# 4_MCU.net
KiCad netlist of a schematic drawn in Altium Designer
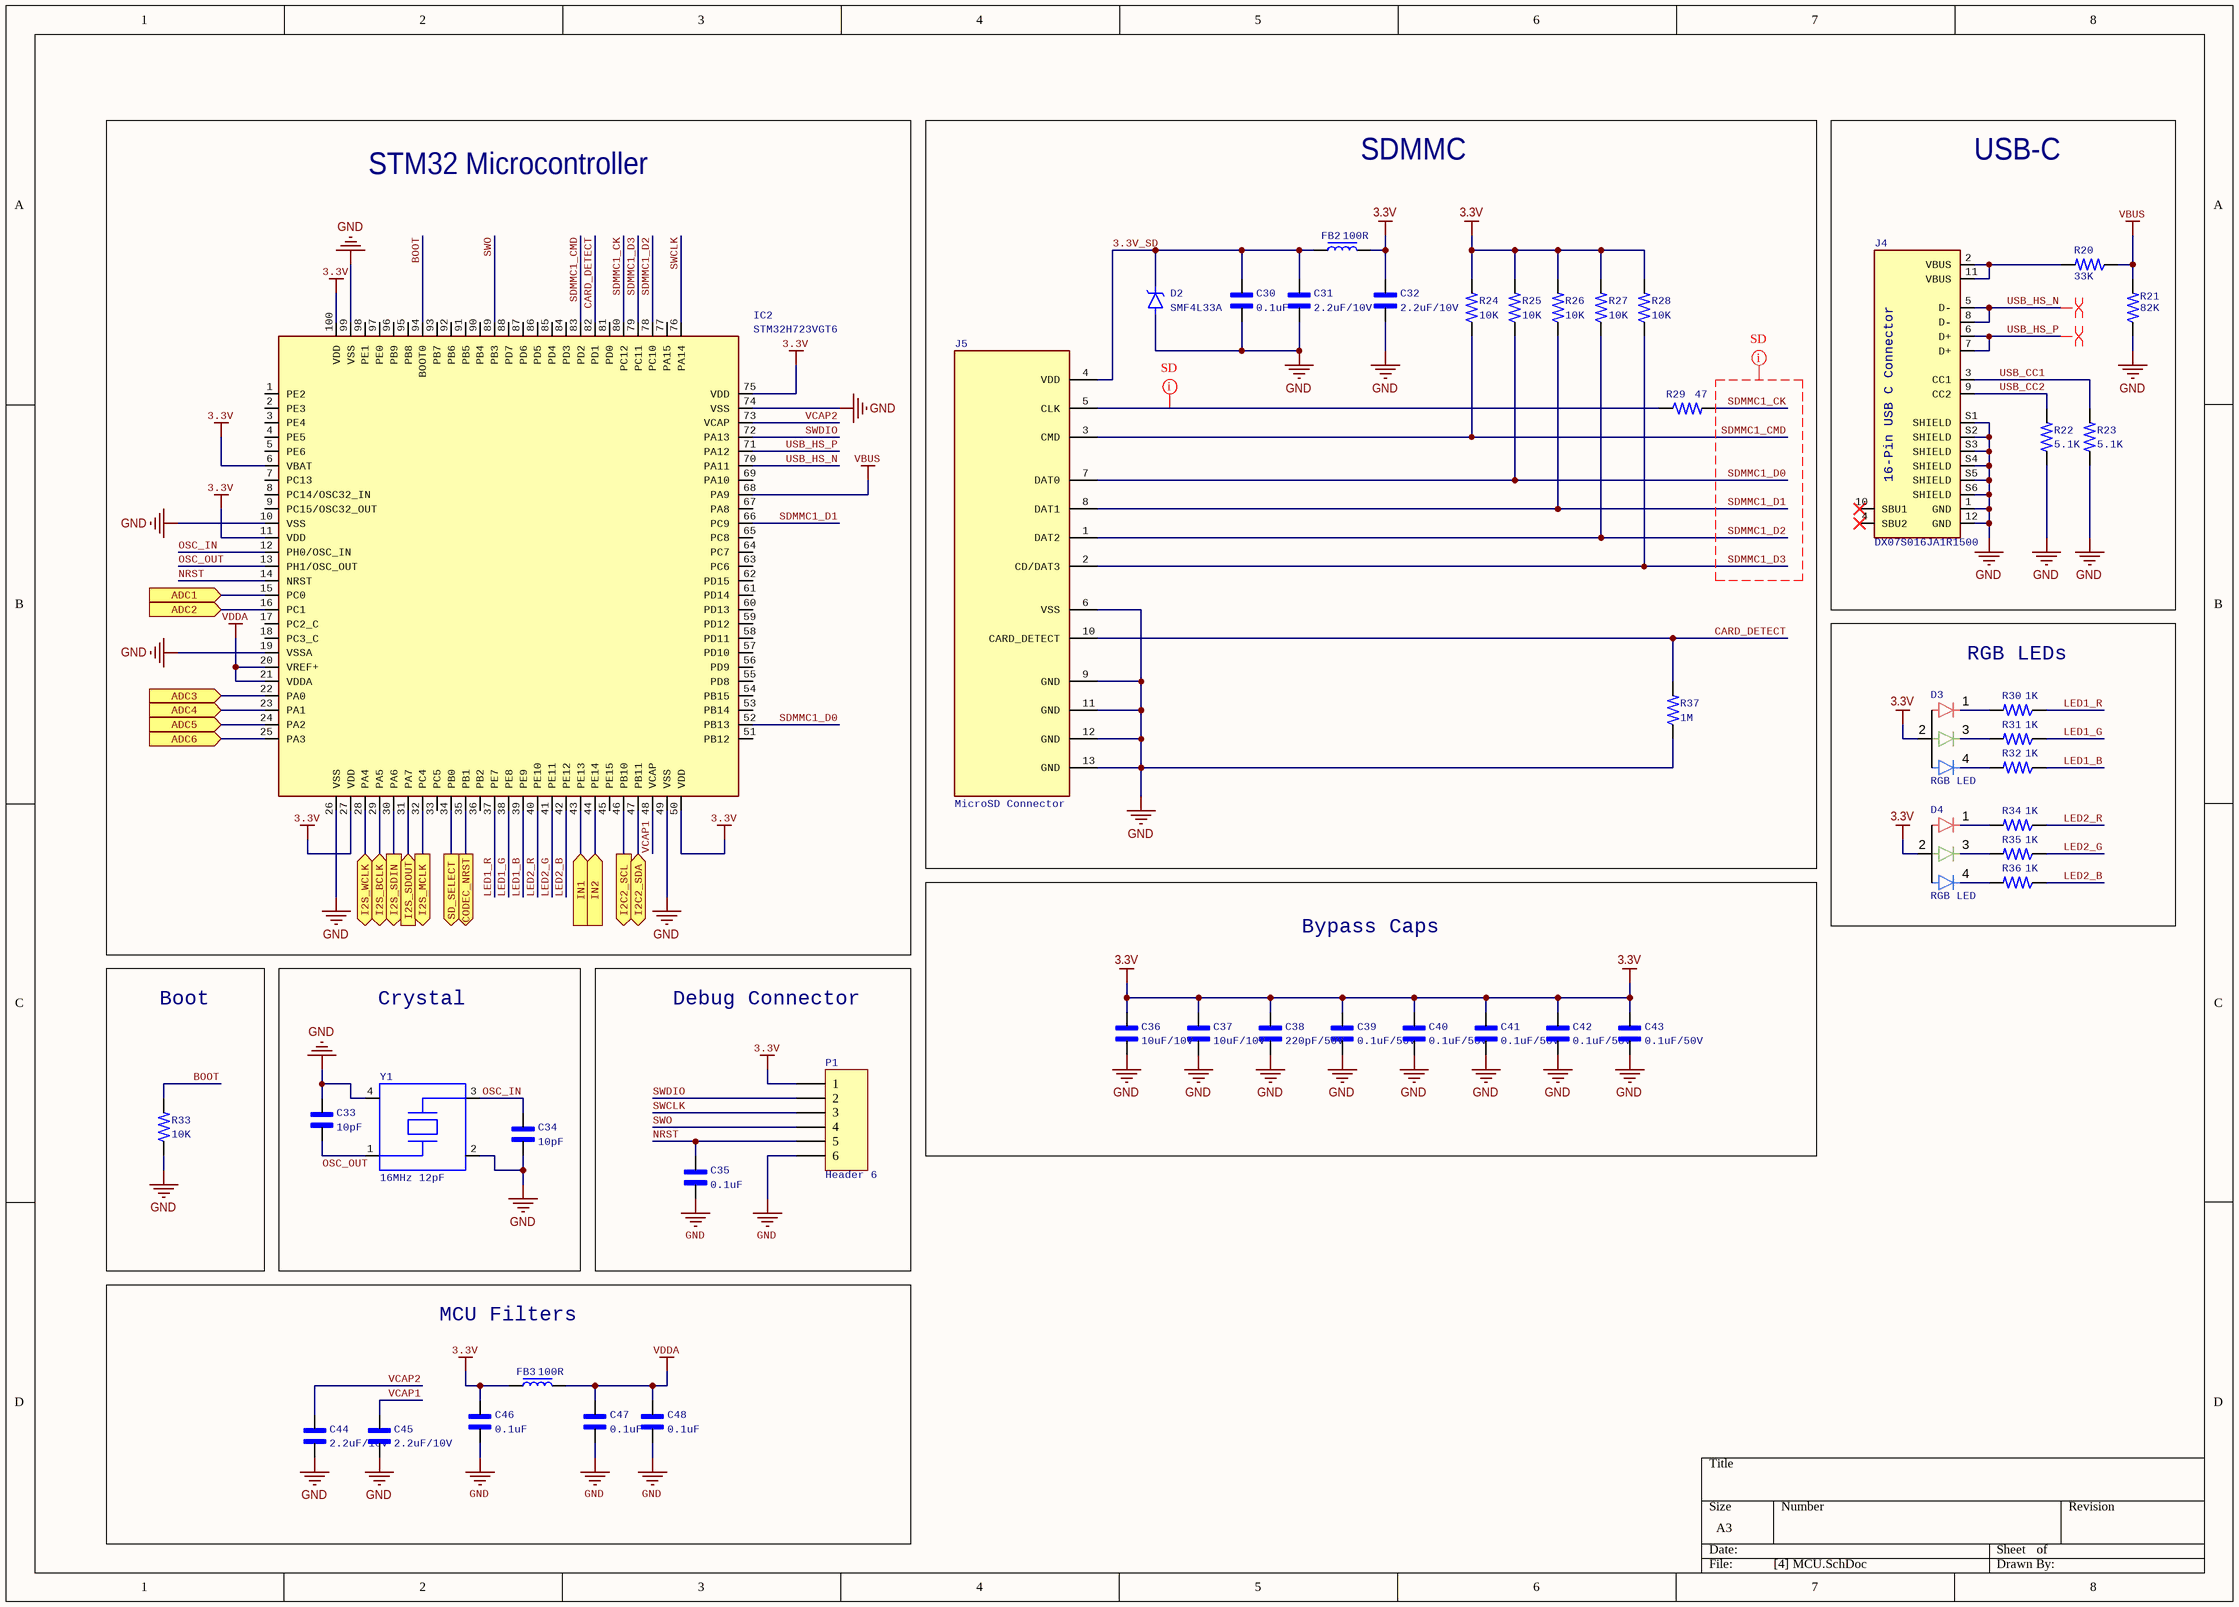
[diagram p0: [4] MCU.SchDoc]

(export (version "E")
  (design (tool "Eeschema 10.0.6"))
  (components
    (comp (ref "C30")
      (value "0.1uF")
      (footprint "C0603")
      (description "MLCC 0.1uF 50V X5R 10% 0603")
      (fields
        (field (name "MANUFACTURER") "TDK")
        (field (name "MANUFACTURER PART NUMBER") "C1608X5R1H104K080AA")
      )
      (libsource (lib "Capacitors") (part "C0603 0.1uF/50V"))
    )
    (comp (ref "C31")
      (value "2.2uF/10V")
      (footprint "C0603")
      (description "MLCC 2.2uF 10V X5R 10% 0603")
      (fields
        (field (name "MANUFACTURER") "Samsung")
        (field (name "MANUFACTURER PART NUMBER") "CL10A225KP8NNNC")
      )
      (libsource (lib "Capacitors") (part "C0603 2.2uF/10V"))
    )
    (comp (ref "C32")
      (value "2.2uF/10V")
      (footprint "C0603")
      (description "MLCC 2.2uF 10V X5R 10% 0603")
      (fields
        (field (name "MANUFACTURER") "Samsung")
        (field (name "MANUFACTURER PART NUMBER") "CL10A225KP8NNNC")
      )
      (libsource (lib "Capacitors") (part "C0603 2.2uF/10V"))
    )
    (comp (ref "C33")
      (value "10pF")
      (footprint "C0603")
      (description "MLCC 10pF 50V X7R 10% 0603")
      (fields
        (field (name "MANUFACTURER") "KEMET")
        (field (name "MANUFACTURER PART NUMBER") "C0603C100K5RACTU")
      )
      (libsource (lib "") (part "C0603 10pF/50V_1"))
    )
    (comp (ref "C34")
      (value "10pF")
      (footprint "C0603")
      (description "MLCC 10pF 50V X7R 10% 0603")
      (fields
        (field (name "MANUFACTURER") "KEMET")
        (field (name "MANUFACTURER PART NUMBER") "C0603C100K5RACTU")
      )
      (libsource (lib "Capacitors") (part "C0603 10pF/50V"))
    )
    (comp (ref "C35")
      (value "0.1uF")
      (footprint "C0603")
      (description "MLCC 0.1uF 50V X5R 10% 0603")
      (fields
        (field (name "MANUFACTURER") "TDK")
        (field (name "MANUFACTURER PART NUMBER") "C1608X5R1H104K080AA")
      )
      (libsource (lib "Capacitors") (part "C0603 0.1uF/50V"))
    )
    (comp (ref "C36")
      (value "10uF/10V")
      (footprint "C0603")
      (description "MLCC 10uF 10V X5R 20% 0603")
      (fields
        (field (name "MANUFACTURER") "KEMET")
        (field (name "MANUFACTURER PART NUMBER") "C0603C106M8PAC7867")
      )
      (libsource (lib "Capacitors") (part "C0603 10uF/10V"))
    )
    (comp (ref "C37")
      (value "10uF/10V")
      (footprint "C0603")
      (description "MLCC 10uF 10V X5R 20% 0603")
      (fields
        (field (name "MANUFACTURER") "KEMET")
        (field (name "MANUFACTURER PART NUMBER") "C0603C106M8PAC7867")
      )
      (libsource (lib "Capacitors") (part "C0603 10uF/10V"))
    )
    (comp (ref "C38")
      (value "220pF/50V")
      (footprint "C0603")
      (description "MLCC 220pF 50V X7R 10% 0603")
      (fields
        (field (name "MANUFACTURER") "KEMET")
        (field (name "MANUFACTURER PART NUMBER") "C0603C221K5RACTU")
      )
      (libsource (lib "Capacitors") (part "C0603 220pF/50V"))
    )
    (comp (ref "C39")
      (value "0.1uF/50V")
      (footprint "C0603")
      (description "MLCC 0.1uF 50V X5R 10% 0603")
      (fields
        (field (name "MANUFACTURER") "TDK")
        (field (name "MANUFACTURER PART NUMBER") "C1608X5R1H104K080AA")
      )
      (libsource (lib "Capacitors") (part "C0603 0.1uF/50V"))
    )
    (comp (ref "C40")
      (value "0.1uF/50V")
      (footprint "C0603")
      (description "MLCC 0.1uF 50V X5R 10% 0603")
      (fields
        (field (name "MANUFACTURER") "TDK")
        (field (name "MANUFACTURER PART NUMBER") "C1608X5R1H104K080AA")
      )
      (libsource (lib "Capacitors") (part "C0603 0.1uF/50V"))
    )
    (comp (ref "C41")
      (value "0.1uF/50V")
      (footprint "C0603")
      (description "MLCC 0.1uF 50V X5R 10% 0603")
      (fields
        (field (name "MANUFACTURER") "TDK")
        (field (name "MANUFACTURER PART NUMBER") "C1608X5R1H104K080AA")
      )
      (libsource (lib "Capacitors") (part "C0603 0.1uF/50V"))
    )
    (comp (ref "C42")
      (value "0.1uF/50V")
      (footprint "C0603")
      (description "MLCC 0.1uF 50V X5R 10% 0603")
      (fields
        (field (name "MANUFACTURER") "TDK")
        (field (name "MANUFACTURER PART NUMBER") "C1608X5R1H104K080AA")
      )
      (libsource (lib "Capacitors") (part "C0603 0.1uF/50V"))
    )
    (comp (ref "C43")
      (value "0.1uF/50V")
      (footprint "C0603")
      (description "MLCC 0.1uF 50V X5R 10% 0603")
      (fields
        (field (name "MANUFACTURER") "TDK")
        (field (name "MANUFACTURER PART NUMBER") "C1608X5R1H104K080AA")
      )
      (libsource (lib "Capacitors") (part "C0603 0.1uF/50V"))
    )
    (comp (ref "C44")
      (value "2.2uF/10V")
      (footprint "C0603")
      (description "MLCC 2.2uF 10V X5R 10% 0603")
      (fields
        (field (name "MANUFACTURER") "Samsung")
        (field (name "MANUFACTURER PART NUMBER") "CL10A225KP8NNNC")
      )
      (libsource (lib "Capacitors") (part "C0603 2.2uF/10V"))
    )
    (comp (ref "C45")
      (value "2.2uF/10V")
      (footprint "C0603")
      (description "MLCC 2.2uF 10V X5R 10% 0603")
      (fields
        (field (name "MANUFACTURER") "Samsung")
        (field (name "MANUFACTURER PART NUMBER") "CL10A225KP8NNNC")
      )
      (libsource (lib "Capacitors") (part "C0603 2.2uF/10V"))
    )
    (comp (ref "C46")
      (value "0.1uF")
      (footprint "C0603")
      (description "MLCC 0.1uF 50V X5R 10% 0603")
      (fields
        (field (name "MANUFACTURER") "TDK")
        (field (name "MANUFACTURER PART NUMBER") "C1608X5R1H104K080AA")
      )
      (libsource (lib "Capacitors") (part "C0603 0.1uF/50V"))
    )
    (comp (ref "C47")
      (value "0.1uF")
      (footprint "C0603")
      (description "MLCC 0.1uF 50V X5R 10% 0603")
      (fields
        (field (name "MANUFACTURER") "TDK")
        (field (name "MANUFACTURER PART NUMBER") "C1608X5R1H104K080AA")
      )
      (libsource (lib "Capacitors") (part "C0603 0.1uF/50V"))
    )
    (comp (ref "C48")
      (value "0.1uF")
      (footprint "C0603")
      (description "MLCC 0.1uF 50V X5R 10% 0603")
      (fields
        (field (name "MANUFACTURER") "TDK")
        (field (name "MANUFACTURER PART NUMBER") "C1608X5R1H104K080AA")
      )
      (libsource (lib "Capacitors") (part "C0603 0.1uF/50V"))
    )
    (comp (ref "D2")
      (value "SMF4L33A")
      (footprint "SOD-123FL")
      (description "TVS DIODE, 2KW, 33V, UNIDIR, SOD-123FL")
      (fields (field (name "MANUFACTURER") "Littelfuse"))
      (libsource (lib "DiscreteSemi") (part "ESD Diode SMF4L33A"))
    )
    (comp (ref "D3")
      (value "RGB LED")
      (footprint "RGB LED CA")
      (description "LED RGB CLEAR T-1 3/4 T/H CA")
      (fields
        (field (name "MANUFACTURER") "Kingbright")
        (field (name "MANUFACTURER PART NUMBER") "WP154A4SEJ3VBDZGC/CA")
      )
      (libsource (lib "LED") (part "RGB LED CA PTH"))
    )
    (comp (ref "D4")
      (value "RGB LED")
      (footprint "RGB LED CA")
      (description "LED RGB CLEAR T-1 3/4 T/H CA")
      (fields
        (field (name "MANUFACTURER") "Kingbright")
        (field (name "MANUFACTURER PART NUMBER") "WP154A4SEJ3VBDZGC/CA")
      )
      (libsource (lib "LED") (part "RGB LED CA PTH"))
    )
    (comp (ref "FB2")
      (value "100R")
      (footprint "FB_0603")
      (description "Ferrite Bead SMD 0603")
      (libsource (lib "Schematic-Lib-PhilsLab") (part "FB_0603"))
    )
    (comp (ref "FB3")
      (value "100R")
      (footprint "FB_0603")
      (description "Ferrite Bead SMD 0603")
      (libsource (lib "Schematic-Lib-PhilsLab") (part "FB_0603"))
    )
    (comp (ref "IC2")
      (value "STM32H723VGT6")
      (footprint "QFP-100")
      (description "MCU 32-bit ARM Cortex M7 RISC 1MB Flash 1.8V/2.5V/3.3V 100-Pin LQFP Tray")
      (fields (field (name "MANUFACTURER") "STMicroelectronics"))
      (libsource (lib "MCUs") (part "STM32H723VGT6"))
    )
    (comp (ref "J4")
      (value "DX07S016JA1R1500")
      (footprint "USB-C_JAE_DX07S016JA1R1500")
      (description "USB-C (USB TYPE-C) USB 2.0 Receptacle Connector 24 (16+8 Dummy) SMT, Right Angle; Through Hole")
      (fields (field (name "MANUFACTURER") "JAE Electronics"))
      (libsource (lib "Connectors") (part "USB C 16-Pin"))
    )
    (comp (ref "J5")
      (value "MicroSD Connector")
      (footprint "DM3CSSF")
      (description "Connector, Memory, Micro Sd, DM3CS-SF")
      (fields (field (name "MANUFACTURER") "Hirose") (field (name "MANUFACTURER PART NUMBER") "DM3CS-SF"))
      (libsource (lib "Connectors") (part "DM3CS-SF"))
    )
    (comp (ref "P1")
      (value "Header 6")
      (footprint "HDR1X6")
      (description "Header, 6-Pin")
      (fields (field (name "PUBLISHER") "Altium Limited"))
      (libsource (lib "Miscellaneous Connectors") (part "Header 6"))
    )
    (comp (ref "R20")
      (value "33K")
      (footprint "R0603")
      (description "RES 0603 33K 1% 1/10W")
      (fields
        (field (name "MANUFACTURER") "Yageo")
        (field (name "MANUFACTURER PART NUMBER") "AC0603FR-1333KL")
      )
      (libsource (lib "Resistors") (part "R0603 33K"))
    )
    (comp (ref "R21")
      (value "82K")
      (footprint "R0603")
      (description "RES 0603 82K OHM 0.5% 1/10W")
      (fields
        (field (name "MANUFACTURER") "Yageo")
        (field (name "MANUFACTURER PART NUMBER") "RC0603FR-0782KL")
      )
      (libsource (lib "Resistors") (part "R0603 82K"))
    )
    (comp (ref "R22")
      (value "5.1K")
      (footprint "R0603")
      (description "RES 0603 5.1K OHM 1% 1/10W")
      (fields
        (field (name "MANUFACTURER") "Yageo")
        (field (name "MANUFACTURER PART NUMBER") "RC0603FR-075K1L")
      )
      (libsource (lib "Resistors") (part "R0603 5.1K"))
    )
    (comp (ref "R23")
      (value "5.1K")
      (footprint "R0603")
      (description "RES 0603 5.1K OHM 1% 1/10W")
      (fields
        (field (name "MANUFACTURER") "Yageo")
        (field (name "MANUFACTURER PART NUMBER") "RC0603FR-075K1L")
      )
      (libsource (lib "Resistors") (part "R0603 5.1K"))
    )
    (comp (ref "R24")
      (value "10K")
      (footprint "R0603")
      (description "RES 0603 10K OHM 1% 1/10W")
      (fields
        (field (name "MANUFACTURER") "Yageo")
        (field (name "MANUFACTURER PART NUMBER") "RC0603FR-1310KL")
      )
      (libsource (lib "Resistors") (part "R0603 10K"))
    )
    (comp (ref "R25")
      (value "10K")
      (footprint "R0603")
      (description "RES 0603 10K OHM 1% 1/10W")
      (fields
        (field (name "MANUFACTURER") "Yageo")
        (field (name "MANUFACTURER PART NUMBER") "RC0603FR-1310KL")
      )
      (libsource (lib "Resistors") (part "R0603 10K"))
    )
    (comp (ref "R26")
      (value "10K")
      (footprint "R0603")
      (description "RES 0603 10K OHM 1% 1/10W")
      (fields
        (field (name "MANUFACTURER") "Yageo")
        (field (name "MANUFACTURER PART NUMBER") "RC0603FR-1310KL")
      )
      (libsource (lib "Resistors") (part "R0603 10K"))
    )
    (comp (ref "R27")
      (value "10K")
      (footprint "R0603")
      (description "RES 0603 10K OHM 1% 1/10W")
      (fields
        (field (name "MANUFACTURER") "Yageo")
        (field (name "MANUFACTURER PART NUMBER") "RC0603FR-1310KL")
      )
      (libsource (lib "Resistors") (part "R0603 10K"))
    )
    (comp (ref "R28")
      (value "10K")
      (footprint "R0603")
      (description "RES 0603 10K OHM 1% 1/10W")
      (fields
        (field (name "MANUFACTURER") "Yageo")
        (field (name "MANUFACTURER PART NUMBER") "RC0603FR-1310KL")
      )
      (libsource (lib "Resistors") (part "R0603 10K"))
    )
    (comp (ref "R29")
      (value "47")
      (footprint "R0603")
      (description "RES 0603 47 1% 1/10W")
      (fields
        (field (name "MANUFACTURER") "Yageo")
        (field (name "MANUFACTURER PART NUMBER") "RC0603FR-0747RL")
      )
      (libsource (lib "Resistors") (part "R0603 47"))
    )
    (comp (ref "R30")
      (value "1K")
      (footprint "R0603")
      (description "RES 0603 1K OHM 1% 1/10W")
      (fields
        (field (name "MANUFACTURER") "Yageo")
        (field (name "MANUFACTURER PART NUMBER") "RC0603FR-071KL")
      )
      (libsource (lib "Resistors") (part "R0603 1K"))
    )
    (comp (ref "R31")
      (value "1K")
      (footprint "R0603")
      (description "RES 0603 1K OHM 1% 1/10W")
      (fields
        (field (name "MANUFACTURER") "Yageo")
        (field (name "MANUFACTURER PART NUMBER") "RC0603FR-071KL")
      )
      (libsource (lib "Resistors") (part "R0603 1K"))
    )
    (comp (ref "R32")
      (value "1K")
      (footprint "R0603")
      (description "RES 0603 1K OHM 1% 1/10W")
      (fields
        (field (name "MANUFACTURER") "Yageo")
        (field (name "MANUFACTURER PART NUMBER") "RC0603FR-071KL")
      )
      (libsource (lib "Resistors") (part "R0603 1K"))
    )
    (comp (ref "R33")
      (value "10K")
      (footprint "R0603")
      (description "RES 0603 10K OHM 1% 1/10W")
      (fields
        (field (name "MANUFACTURER") "Yageo")
        (field (name "MANUFACTURER PART NUMBER") "RC0603FR-1310KL")
      )
      (libsource (lib "Resistors") (part "R0603 10K"))
    )
    (comp (ref "R34")
      (value "1K")
      (footprint "R0603")
      (description "RES 0603 1K OHM 1% 1/10W")
      (fields
        (field (name "MANUFACTURER") "Yageo")
        (field (name "MANUFACTURER PART NUMBER") "RC0603FR-071KL")
      )
      (libsource (lib "Resistors") (part "R0603 1K"))
    )
    (comp (ref "R35")
      (value "1K")
      (footprint "R0603")
      (description "RES 0603 1K OHM 1% 1/10W")
      (fields
        (field (name "MANUFACTURER") "Yageo")
        (field (name "MANUFACTURER PART NUMBER") "RC0603FR-071KL")
      )
      (libsource (lib "Resistors") (part "R0603 1K"))
    )
    (comp (ref "R36")
      (value "1K")
      (footprint "R0603")
      (description "RES 0603 1K OHM 1% 1/10W")
      (fields
        (field (name "MANUFACTURER") "Yageo")
        (field (name "MANUFACTURER PART NUMBER") "RC0603FR-071KL")
      )
      (libsource (lib "Resistors") (part "R0603 1K"))
    )
    (comp (ref "R37")
      (value "1M")
      (footprint "R0603")
      (description "RES SMD 1M OHM 1% 1/10W 0603")
      (fields
        (field (name "MANUFACTURER") "Yageo")
        (field (name "MANUFACTURER PART NUMBER") "RC0603FR-071ML")
      )
      (libsource (lib "Resistors") (part "R0603 1M"))
    )
    (comp (ref "Y1")
      (value "16MHz 12pF")
      (footprint "XTAL 3.2 x 2.5 mm")
      (description "Crystal 16MHz ±50ppm (Tol) ±100ppm (Stability) 12pF FUND 80Ohm 4-Pin SMD T/R")
      (fields
        (field (name "MANUFACTURER") "Kyocera AVX")
        (field (name "MANUFACTURER PART NUMBER") "CX3225SB16000H0PSTC1")
      )
      (libsource (lib "Clocks") (part "XTAL 16MHz 12pF"))
    )
  )
  (nets
    (net (code "1") (name "/3.3V_SD") (class "Default")
      (node (ref "C30") (pin "1") (pinfunction "1_1") (pintype "passive"))
      (node (ref "C31") (pin "1") (pinfunction "1_1") (pintype "passive"))
      (node (ref "D2") (pin "C") (pinfunction "C_C") (pintype "passive"))
      (node (ref "FB2") (pin "1") (pinfunction "1_1") (pintype "passive"))
      (node (ref "J5") (pin "4") (pinfunction "VDD_4") (pintype "passive"))
    )
    (net (code "2") (name "/ADC1") (class "Default")
      (node (ref "IC2") (pin "15") (pinfunction "PC0_15") (pintype "passive"))
    )
    (net (code "3") (name "/ADC2") (class "Default")
      (node (ref "IC2") (pin "16") (pinfunction "PC1_16") (pintype "passive"))
    )
    (net (code "4") (name "/ADC3") (class "Default")
      (node (ref "IC2") (pin "22") (pinfunction "PA0_22") (pintype "passive"))
    )
    (net (code "5") (name "/ADC4") (class "Default")
      (node (ref "IC2") (pin "23") (pinfunction "PA1_23") (pintype "passive"))
    )
    (net (code "6") (name "/ADC5") (class "Default")
      (node (ref "IC2") (pin "24") (pinfunction "PA2_24") (pintype "passive"))
    )
    (net (code "7") (name "/ADC6") (class "Default")
      (node (ref "IC2") (pin "25") (pinfunction "PA3_25") (pintype "passive"))
    )
    (net (code "8") (name "/BOOT") (class "Default")
      (node (ref "IC2") (pin "94") (pinfunction "BOOT0_94") (pintype "passive"))
      (node (ref "R33") (pin "2") (pinfunction "2_2") (pintype "passive"))
    )
    (net (code "9") (name "/CARD_DETECT") (class "Default")
      (node (ref "IC2") (pin "82") (pinfunction "PD1_82") (pintype "passive"))
      (node (ref "J5") (pin "10") (pinfunction "CARD_DETECT_10") (pintype "passive"))
      (node (ref "R37") (pin "2") (pinfunction "2_2") (pintype "passive"))
    )
    (net (code "10") (name "/CODEC_NRST") (class "Default")
      (node (ref "IC2") (pin "35") (pinfunction "PB1_35") (pintype "passive"))
    )
    (net (code "11") (name "/I2C2_SCL") (class "Default")
      (node (ref "IC2") (pin "46") (pinfunction "PB10_46") (pintype "passive"))
    )
    (net (code "12") (name "/I2C2_SDA") (class "Default")
      (node (ref "IC2") (pin "47") (pinfunction "PB11_47") (pintype "passive"))
    )
    (net (code "13") (name "/I2S_BCLK") (class "Default")
      (node (ref "IC2") (pin "29") (pinfunction "PA5_29") (pintype "passive"))
    )
    (net (code "14") (name "/I2S_MCLK") (class "Default")
      (node (ref "IC2") (pin "32") (pinfunction "PC4_32") (pintype "passive"))
    )
    (net (code "15") (name "/I2S_SDIN") (class "Default")
      (node (ref "IC2") (pin "30") (pinfunction "PA6_30") (pintype "passive"))
    )
    (net (code "16") (name "/I2S_SDOUT") (class "Default")
      (node (ref "IC2") (pin "31") (pinfunction "PA7_31") (pintype "passive"))
    )
    (net (code "17") (name "/I2S_WCLK") (class "Default")
      (node (ref "IC2") (pin "28") (pinfunction "PA4_28") (pintype "passive"))
    )
    (net (code "18") (name "/IN1") (class "Default")
      (node (ref "IC2") (pin "43") (pinfunction "PE13_43") (pintype "passive"))
    )
    (net (code "19") (name "/IN2") (class "Default")
      (node (ref "IC2") (pin "44") (pinfunction "PE14_44") (pintype "passive"))
    )
    (net (code "20") (name "/LED1_B") (class "Default")
      (node (ref "IC2") (pin "39") (pinfunction "PE9_39") (pintype "passive"))
      (node (ref "R32") (pin "1") (pinfunction "1_1") (pintype "passive"))
    )
    (net (code "21") (name "/LED1_G") (class "Default")
      (node (ref "IC2") (pin "38") (pinfunction "PE8_38") (pintype "passive"))
      (node (ref "R31") (pin "1") (pinfunction "1_1") (pintype "passive"))
    )
    (net (code "22") (name "/LED1_R") (class "Default")
      (node (ref "IC2") (pin "37") (pinfunction "PE7_37") (pintype "passive"))
      (node (ref "R30") (pin "1") (pinfunction "1_1") (pintype "passive"))
    )
    (net (code "23") (name "/LED2_B") (class "Default")
      (node (ref "IC2") (pin "42") (pinfunction "PE12_42") (pintype "passive"))
      (node (ref "R36") (pin "1") (pinfunction "1_1") (pintype "passive"))
    )
    (net (code "24") (name "/LED2_G") (class "Default")
      (node (ref "IC2") (pin "41") (pinfunction "PE11_41") (pintype "passive"))
      (node (ref "R35") (pin "1") (pinfunction "1_1") (pintype "passive"))
    )
    (net (code "25") (name "/LED2_R") (class "Default")
      (node (ref "IC2") (pin "40") (pinfunction "PE10_40") (pintype "passive"))
      (node (ref "R34") (pin "1") (pinfunction "1_1") (pintype "passive"))
    )
    (net (code "26") (name "/NRST") (class "Default")
      (node (ref "C35") (pin "1") (pinfunction "1_1") (pintype "passive"))
      (node (ref "IC2") (pin "14") (pinfunction "NRST_14") (pintype "passive"))
      (node (ref "P1") (pin "5") (pinfunction "5_5") (pintype "passive"))
    )
    (net (code "27") (name "/OSC_IN") (class "Default")
      (node (ref "C34") (pin "2") (pinfunction "2_2") (pintype "passive"))
      (node (ref "IC2") (pin "12") (pinfunction "PH0/OSC_IN_12") (pintype "passive"))
      (node (ref "Y1") (pin "3") (pinfunction "3_3") (pintype "passive"))
    )
    (net (code "28") (name "/OSC_OUT") (class "Default")
      (node (ref "C33") (pin "2") (pinfunction "2_2") (pintype "passive"))
      (node (ref "IC2") (pin "13") (pinfunction "PH1/OSC_OUT_13") (pintype "passive"))
      (node (ref "Y1") (pin "1") (pinfunction "1_1") (pintype "passive"))
    )
    (net (code "29") (name "/SDMMC1_CK") (class "Default")
      (node (ref "IC2") (pin "80") (pinfunction "PC12_80") (pintype "passive"))
      (node (ref "R29") (pin "2") (pinfunction "2_2") (pintype "passive"))
    )
    (net (code "30") (name "/SDMMC1_CMD") (class "Default")
      (node (ref "IC2") (pin "83") (pinfunction "PD2_83") (pintype "passive"))
      (node (ref "J5") (pin "3") (pinfunction "CMD_3") (pintype "passive"))
      (node (ref "R24") (pin "1") (pinfunction "1_1") (pintype "passive"))
    )
    (net (code "31") (name "/SDMMC1_D0") (class "Default")
      (node (ref "IC2") (pin "52") (pinfunction "PB13_52") (pintype "passive"))
      (node (ref "J5") (pin "7") (pinfunction "DAT0_7") (pintype "passive"))
      (node (ref "R25") (pin "1") (pinfunction "1_1") (pintype "passive"))
    )
    (net (code "32") (name "/SDMMC1_D1") (class "Default")
      (node (ref "IC2") (pin "66") (pinfunction "PC9_66") (pintype "passive"))
      (node (ref "J5") (pin "8") (pinfunction "DAT1_8") (pintype "passive"))
      (node (ref "R26") (pin "1") (pinfunction "1_1") (pintype "passive"))
    )
    (net (code "33") (name "/SDMMC1_D2") (class "Default")
      (node (ref "IC2") (pin "78") (pinfunction "PC10_78") (pintype "passive"))
      (node (ref "J5") (pin "1") (pinfunction "DAT2_1") (pintype "passive"))
      (node (ref "R27") (pin "1") (pinfunction "1_1") (pintype "passive"))
    )
    (net (code "34") (name "/SDMMC1_D3") (class "Default")
      (node (ref "IC2") (pin "79") (pinfunction "PC11_79") (pintype "passive"))
      (node (ref "J5") (pin "2") (pinfunction "CD/DAT3_2") (pintype "passive"))
      (node (ref "R28") (pin "1") (pinfunction "1_1") (pintype "passive"))
    )
    (net (code "35") (name "/SD_SELECT") (class "Default")
      (node (ref "IC2") (pin "34") (pinfunction "PB0_34") (pintype "passive"))
    )
    (net (code "36") (name "/SWCLK") (class "Default")
      (node (ref "IC2") (pin "76") (pinfunction "PA14_76") (pintype "passive"))
      (node (ref "P1") (pin "3") (pinfunction "3_3") (pintype "passive"))
    )
    (net (code "37") (name "/SWDIO") (class "Default")
      (node (ref "IC2") (pin "72") (pinfunction "PA13_72") (pintype "passive"))
      (node (ref "P1") (pin "2") (pinfunction "2_2") (pintype "passive"))
    )
    (net (code "38") (name "/SWO") (class "Default")
      (node (ref "IC2") (pin "89") (pinfunction "PB3_89") (pintype "passive"))
      (node (ref "P1") (pin "4") (pinfunction "4_4") (pintype "passive"))
    )
    (net (code "39") (name "/USB_CC1") (class "Default")
      (node (ref "J4") (pin "3") (pinfunction "CC1_3") (pintype "passive"))
      (node (ref "R23") (pin "2") (pinfunction "2_2") (pintype "passive"))
    )
    (net (code "40") (name "/USB_CC2") (class "Default")
      (node (ref "J4") (pin "9") (pinfunction "CC2_9") (pintype "passive"))
      (node (ref "R22") (pin "2") (pinfunction "2_2") (pintype "passive"))
    )
    (net (code "41") (name "/USB_HS_N") (class "Default")
      (node (ref "IC2") (pin "70") (pinfunction "PA11_70") (pintype "passive"))
      (node (ref "J4") (pin "5") (pinfunction "D-_5") (pintype "passive"))
      (node (ref "J4") (pin "8") (pinfunction "D-_8") (pintype "passive"))
    )
    (net (code "42") (name "/USB_HS_P") (class "Default")
      (node (ref "IC2") (pin "71") (pinfunction "PA12_71") (pintype "passive"))
      (node (ref "J4") (pin "6") (pinfunction "D+_6") (pintype "passive"))
      (node (ref "J4") (pin "7") (pinfunction "D+_7") (pintype "passive"))
    )
    (net (code "43") (name "/VCAP1") (class "Default")
      (node (ref "C45") (pin "1") (pinfunction "1_1") (pintype "passive"))
      (node (ref "IC2") (pin "48") (pinfunction "VCAP_48") (pintype "passive"))
    )
    (net (code "44") (name "/VCAP2") (class "Default")
      (node (ref "C44") (pin "1") (pinfunction "1_1") (pintype "passive"))
      (node (ref "IC2") (pin "73") (pinfunction "VCAP_73") (pintype "passive"))
    )
    (net (code "45") (name "3.3V") (class "Default")
      (node (ref "C32") (pin "1") (pinfunction "1_1") (pintype "passive"))
      (node (ref "C36") (pin "1") (pinfunction "1_1") (pintype "passive"))
      (node (ref "C37") (pin "1") (pinfunction "1_1") (pintype "passive"))
      (node (ref "C38") (pin "1") (pinfunction "1_1") (pintype "passive"))
      (node (ref "C39") (pin "1") (pinfunction "1_1") (pintype "passive"))
      (node (ref "C40") (pin "1") (pinfunction "1_1") (pintype "passive"))
      (node (ref "C41") (pin "1") (pinfunction "1_1") (pintype "passive"))
      (node (ref "C42") (pin "1") (pinfunction "1_1") (pintype "passive"))
      (node (ref "C43") (pin "1") (pinfunction "1_1") (pintype "passive"))
      (node (ref "C46") (pin "1") (pinfunction "1_1") (pintype "passive"))
      (node (ref "D3") (pin "2") (pinfunction "2_2") (pintype "passive"))
      (node (ref "D4") (pin "2") (pinfunction "2_2") (pintype "passive"))
      (node (ref "FB2") (pin "2") (pinfunction "2_2") (pintype "passive"))
      (node (ref "FB3") (pin "1") (pinfunction "1_1") (pintype "passive"))
      (node (ref "IC2") (pin "100") (pinfunction "VDD_100") (pintype "passive"))
      (node (ref "IC2") (pin "11") (pinfunction "VDD_11") (pintype "passive"))
      (node (ref "IC2") (pin "27") (pinfunction "VDD_27") (pintype "passive"))
      (node (ref "IC2") (pin "50") (pinfunction "VDD_50") (pintype "passive"))
      (node (ref "IC2") (pin "6") (pinfunction "VBAT_6") (pintype "passive"))
      (node (ref "IC2") (pin "75") (pinfunction "VDD_75") (pintype "passive"))
      (node (ref "P1") (pin "1") (pinfunction "1_1") (pintype "passive"))
      (node (ref "R24") (pin "2") (pinfunction "2_2") (pintype "passive"))
      (node (ref "R25") (pin "2") (pinfunction "2_2") (pintype "passive"))
      (node (ref "R26") (pin "2") (pinfunction "2_2") (pintype "passive"))
      (node (ref "R27") (pin "2") (pinfunction "2_2") (pintype "passive"))
      (node (ref "R28") (pin "2") (pinfunction "2_2") (pintype "passive"))
    )
    (net (code "46") (name "GND") (class "Default")
      (node (ref "C30") (pin "2") (pinfunction "2_2") (pintype "passive"))
      (node (ref "C31") (pin "2") (pinfunction "2_2") (pintype "passive"))
      (node (ref "C32") (pin "2") (pinfunction "2_2") (pintype "passive"))
      (node (ref "C33") (pin "1") (pinfunction "1_1") (pintype "passive"))
      (node (ref "C34") (pin "1") (pinfunction "1_1") (pintype "passive"))
      (node (ref "C35") (pin "2") (pinfunction "2_2") (pintype "passive"))
      (node (ref "C36") (pin "2") (pinfunction "2_2") (pintype "passive"))
      (node (ref "C37") (pin "2") (pinfunction "2_2") (pintype "passive"))
      (node (ref "C38") (pin "2") (pinfunction "2_2") (pintype "passive"))
      (node (ref "C39") (pin "2") (pinfunction "2_2") (pintype "passive"))
      (node (ref "C40") (pin "2") (pinfunction "2_2") (pintype "passive"))
      (node (ref "C41") (pin "2") (pinfunction "2_2") (pintype "passive"))
      (node (ref "C42") (pin "2") (pinfunction "2_2") (pintype "passive"))
      (node (ref "C43") (pin "2") (pinfunction "2_2") (pintype "passive"))
      (node (ref "C44") (pin "2") (pinfunction "2_2") (pintype "passive"))
      (node (ref "C45") (pin "2") (pinfunction "2_2") (pintype "passive"))
      (node (ref "C46") (pin "2") (pinfunction "2_2") (pintype "passive"))
      (node (ref "C47") (pin "2") (pinfunction "2_2") (pintype "passive"))
      (node (ref "C48") (pin "2") (pinfunction "2_2") (pintype "passive"))
      (node (ref "D2") (pin "A") (pinfunction "A_A") (pintype "passive"))
      (node (ref "IC2") (pin "10") (pinfunction "VSS_10") (pintype "passive"))
      (node (ref "IC2") (pin "19") (pinfunction "VSSA_19") (pintype "passive"))
      (node (ref "IC2") (pin "26") (pinfunction "VSS_26") (pintype "passive"))
      (node (ref "IC2") (pin "49") (pinfunction "VSS_49") (pintype "passive"))
      (node (ref "IC2") (pin "74") (pinfunction "VSS_74") (pintype "passive"))
      (node (ref "IC2") (pin "99") (pinfunction "VSS_99") (pintype "passive"))
      (node (ref "J4") (pin "1") (pinfunction "GND_1") (pintype "power_in"))
      (node (ref "J4") (pin "12") (pinfunction "GND_12") (pintype "power_in"))
      (node (ref "J4") (pin "S1") (pinfunction "SHIELD_S1") (pintype "passive"))
      (node (ref "J4") (pin "S2") (pinfunction "SHIELD_S2") (pintype "passive"))
      (node (ref "J4") (pin "S3") (pinfunction "SHIELD_S3") (pintype "passive"))
      (node (ref "J4") (pin "S4") (pinfunction "SHIELD_S4") (pintype "passive"))
      (node (ref "J4") (pin "S5") (pinfunction "SHIELD_S5") (pintype "passive"))
      (node (ref "J4") (pin "S6") (pinfunction "SHIELD_S6") (pintype "passive"))
      (node (ref "J5") (pin "11") (pinfunction "GND_11") (pintype "passive"))
      (node (ref "J5") (pin "12") (pinfunction "GND_12") (pintype "passive"))
      (node (ref "J5") (pin "13") (pinfunction "GND_13") (pintype "passive"))
      (node (ref "J5") (pin "6") (pinfunction "VSS_6") (pintype "passive"))
      (node (ref "J5") (pin "9") (pinfunction "GND_9") (pintype "passive"))
      (node (ref "P1") (pin "6") (pinfunction "6_6") (pintype "passive"))
      (node (ref "R21") (pin "1") (pinfunction "1_1") (pintype "passive"))
      (node (ref "R22") (pin "1") (pinfunction "1_1") (pintype "passive"))
      (node (ref "R23") (pin "1") (pinfunction "1_1") (pintype "passive"))
      (node (ref "R33") (pin "1") (pinfunction "1_1") (pintype "passive"))
      (node (ref "R37") (pin "1") (pinfunction "1_1") (pintype "passive"))
      (node (ref "Y1") (pin "2") (pinfunction "2_2") (pintype "passive"))
      (node (ref "Y1") (pin "4") (pinfunction "4_4") (pintype "passive"))
    )
    (net (code "47") (name "Net-(D3-Pad3)") (class "Default")
      (node (ref "D3") (pin "3") (pinfunction "3_3") (pintype "passive"))
      (node (ref "R31") (pin "2") (pinfunction "2_2") (pintype "passive"))
    )
    (net (code "48") (name "Net-(D3-Pad4)") (class "Default")
      (node (ref "D3") (pin "4") (pinfunction "4_4") (pintype "passive"))
      (node (ref "R32") (pin "2") (pinfunction "2_2") (pintype "passive"))
    )
    (net (code "49") (name "Net-(D3-R)") (class "Default")
      (node (ref "D3") (pin "1") (pinfunction "R_1") (pintype "passive"))
      (node (ref "R30") (pin "2") (pinfunction "2_2") (pintype "passive"))
    )
    (net (code "50") (name "Net-(D4-Pad3)") (class "Default")
      (node (ref "D4") (pin "3") (pinfunction "3_3") (pintype "passive"))
      (node (ref "R35") (pin "2") (pinfunction "2_2") (pintype "passive"))
    )
    (net (code "51") (name "Net-(D4-Pad4)") (class "Default")
      (node (ref "D4") (pin "4") (pinfunction "4_4") (pintype "passive"))
      (node (ref "R36") (pin "2") (pinfunction "2_2") (pintype "passive"))
    )
    (net (code "52") (name "Net-(D4-R)") (class "Default")
      (node (ref "D4") (pin "1") (pinfunction "R_1") (pintype "passive"))
      (node (ref "R34") (pin "2") (pinfunction "2_2") (pintype "passive"))
    )
    (net (code "53") (name "Net-(J4-VBUS-Pad11)") (class "Default")
      (node (ref "J4") (pin "11") (pinfunction "VBUS_11") (pintype "power_in"))
      (node (ref "J4") (pin "2") (pinfunction "VBUS_2") (pintype "power_in"))
      (node (ref "R20") (pin "2") (pinfunction "2_2") (pintype "passive"))
    )
    (net (code "54") (name "Net-(J5-CLK)") (class "Default")
      (node (ref "J5") (pin "5") (pinfunction "CLK_5") (pintype "passive"))
      (node (ref "R29") (pin "1") (pinfunction "1_1") (pintype "passive"))
    )
    (net (code "55") (name "VBUS") (class "Default")
      (node (ref "IC2") (pin "68") (pinfunction "PA9_68") (pintype "passive"))
      (node (ref "R20") (pin "1") (pinfunction "1_1") (pintype "passive"))
      (node (ref "R21") (pin "2") (pinfunction "2_2") (pintype "passive"))
    )
    (net (code "56") (name "VDDA") (class "Default")
      (node (ref "C47") (pin "1") (pinfunction "1_1") (pintype "passive"))
      (node (ref "C48") (pin "1") (pinfunction "1_1") (pintype "passive"))
      (node (ref "FB3") (pin "2") (pinfunction "2_2") (pintype "passive"))
      (node (ref "IC2") (pin "20") (pinfunction "VREF+_20") (pintype "passive"))
      (node (ref "IC2") (pin "21") (pinfunction "VDDA_21") (pintype "passive"))
    )
    (net (code "57") (name "unconnected-(IC2-PA8-Pad67)") (class "Default")
      (node (ref "IC2") (pin "67") (pinfunction "PA8_67") (pintype "passive"))
    )
    (net (code "58") (name "unconnected-(IC2-PA10-Pad69)") (class "Default")
      (node (ref "IC2") (pin "69") (pinfunction "PA10_69") (pintype "passive"))
    )
    (net (code "59") (name "unconnected-(IC2-PA15-Pad77)") (class "Default")
      (node (ref "IC2") (pin "77") (pinfunction "PA15_77") (pintype "passive"))
    )
    (net (code "60") (name "unconnected-(IC2-PB2-Pad36)") (class "Default")
      (node (ref "IC2") (pin "36") (pinfunction "PB2_36") (pintype "passive"))
    )
    (net (code "61") (name "unconnected-(IC2-PB4-Pad90)") (class "Default")
      (node (ref "IC2") (pin "90") (pinfunction "PB4_90") (pintype "passive"))
    )
    (net (code "62") (name "unconnected-(IC2-PB5-Pad91)") (class "Default")
      (node (ref "IC2") (pin "91") (pinfunction "PB5_91") (pintype "passive"))
    )
    (net (code "63") (name "unconnected-(IC2-PB6-Pad92)") (class "Default")
      (node (ref "IC2") (pin "92") (pinfunction "PB6_92") (pintype "passive"))
    )
    (net (code "64") (name "unconnected-(IC2-PB7-Pad93)") (class "Default")
      (node (ref "IC2") (pin "93") (pinfunction "PB7_93") (pintype "passive"))
    )
    (net (code "65") (name "unconnected-(IC2-PB8-Pad95)") (class "Default")
      (node (ref "IC2") (pin "95") (pinfunction "PB8_95") (pintype "passive"))
    )
    (net (code "66") (name "unconnected-(IC2-PB9-Pad96)") (class "Default")
      (node (ref "IC2") (pin "96") (pinfunction "PB9_96") (pintype "passive"))
    )
    (net (code "67") (name "unconnected-(IC2-PB12-Pad51)") (class "Default")
      (node (ref "IC2") (pin "51") (pinfunction "PB12_51") (pintype "passive"))
    )
    (net (code "68") (name "unconnected-(IC2-PB14-Pad53)") (class "Default")
      (node (ref "IC2") (pin "53") (pinfunction "PB14_53") (pintype "passive"))
    )
    (net (code "69") (name "unconnected-(IC2-PB15-Pad54)") (class "Default")
      (node (ref "IC2") (pin "54") (pinfunction "PB15_54") (pintype "passive"))
    )
    (net (code "70") (name "unconnected-(IC2-PC2_C-Pad17)") (class "Default")
      (node (ref "IC2") (pin "17") (pinfunction "PC2_C_17") (pintype "passive"))
    )
    (net (code "71") (name "unconnected-(IC2-PC3_C-Pad18)") (class "Default")
      (node (ref "IC2") (pin "18") (pinfunction "PC3_C_18") (pintype "passive"))
    )
    (net (code "72") (name "unconnected-(IC2-PC5-Pad33)") (class "Default")
      (node (ref "IC2") (pin "33") (pinfunction "PC5_33") (pintype "passive"))
    )
    (net (code "73") (name "unconnected-(IC2-PC6-Pad63)") (class "Default")
      (node (ref "IC2") (pin "63") (pinfunction "PC6_63") (pintype "passive"))
    )
    (net (code "74") (name "unconnected-(IC2-PC7-Pad64)") (class "Default")
      (node (ref "IC2") (pin "64") (pinfunction "PC7_64") (pintype "passive"))
    )
    (net (code "75") (name "unconnected-(IC2-PC8-Pad65)") (class "Default")
      (node (ref "IC2") (pin "65") (pinfunction "PC8_65") (pintype "passive"))
    )
    (net (code "76") (name "unconnected-(IC2-PC13-Pad7)") (class "Default")
      (node (ref "IC2") (pin "7") (pinfunction "PC13_7") (pintype "passive"))
    )
    (net (code "77") (name "unconnected-(IC2-PC14{slash}OSC32_IN-Pad8)") (class "Default")
      (node (ref "IC2") (pin "8") (pinfunction "PC14/OSC32_IN_8") (pintype "passive"))
    )
    (net (code "78") (name "unconnected-(IC2-PC15{slash}OSC32_OUT-Pad9)") (class "Default")
      (node (ref "IC2") (pin "9") (pinfunction "PC15/OSC32_OUT_9") (pintype "passive"))
    )
    (net (code "79") (name "unconnected-(IC2-PD0-Pad81)") (class "Default")
      (node (ref "IC2") (pin "81") (pinfunction "PD0_81") (pintype "passive"))
    )
    (net (code "80") (name "unconnected-(IC2-PD3-Pad84)") (class "Default")
      (node (ref "IC2") (pin "84") (pinfunction "PD3_84") (pintype "passive"))
    )
    (net (code "81") (name "unconnected-(IC2-PD4-Pad85)") (class "Default")
      (node (ref "IC2") (pin "85") (pinfunction "PD4_85") (pintype "passive"))
    )
    (net (code "82") (name "unconnected-(IC2-PD5-Pad86)") (class "Default")
      (node (ref "IC2") (pin "86") (pinfunction "PD5_86") (pintype "passive"))
    )
    (net (code "83") (name "unconnected-(IC2-PD6-Pad87)") (class "Default")
      (node (ref "IC2") (pin "87") (pinfunction "PD6_87") (pintype "passive"))
    )
    (net (code "84") (name "unconnected-(IC2-PD7-Pad88)") (class "Default")
      (node (ref "IC2") (pin "88") (pinfunction "PD7_88") (pintype "passive"))
    )
    (net (code "85") (name "unconnected-(IC2-PD8-Pad55)") (class "Default")
      (node (ref "IC2") (pin "55") (pinfunction "PD8_55") (pintype "passive"))
    )
    (net (code "86") (name "unconnected-(IC2-PD9-Pad56)") (class "Default")
      (node (ref "IC2") (pin "56") (pinfunction "PD9_56") (pintype "passive"))
    )
    (net (code "87") (name "unconnected-(IC2-PD10-Pad57)") (class "Default")
      (node (ref "IC2") (pin "57") (pinfunction "PD10_57") (pintype "passive"))
    )
    (net (code "88") (name "unconnected-(IC2-PD11-Pad58)") (class "Default")
      (node (ref "IC2") (pin "58") (pinfunction "PD11_58") (pintype "passive"))
    )
    (net (code "89") (name "unconnected-(IC2-PD12-Pad59)") (class "Default")
      (node (ref "IC2") (pin "59") (pinfunction "PD12_59") (pintype "passive"))
    )
    (net (code "90") (name "unconnected-(IC2-PD13-Pad60)") (class "Default")
      (node (ref "IC2") (pin "60") (pinfunction "PD13_60") (pintype "passive"))
    )
    (net (code "91") (name "unconnected-(IC2-PD14-Pad61)") (class "Default")
      (node (ref "IC2") (pin "61") (pinfunction "PD14_61") (pintype "passive"))
    )
    (net (code "92") (name "unconnected-(IC2-PD15-Pad62)") (class "Default")
      (node (ref "IC2") (pin "62") (pinfunction "PD15_62") (pintype "passive"))
    )
    (net (code "93") (name "unconnected-(IC2-PE0-Pad97)") (class "Default")
      (node (ref "IC2") (pin "97") (pinfunction "PE0_97") (pintype "passive"))
    )
    (net (code "94") (name "unconnected-(IC2-PE1-Pad98)") (class "Default")
      (node (ref "IC2") (pin "98") (pinfunction "PE1_98") (pintype "passive"))
    )
    (net (code "95") (name "unconnected-(IC2-PE2-Pad1)") (class "Default")
      (node (ref "IC2") (pin "1") (pinfunction "PE2_1") (pintype "passive"))
    )
    (net (code "96") (name "unconnected-(IC2-PE3-Pad2)") (class "Default")
      (node (ref "IC2") (pin "2") (pinfunction "PE3_2") (pintype "passive"))
    )
    (net (code "97") (name "unconnected-(IC2-PE4-Pad3)") (class "Default")
      (node (ref "IC2") (pin "3") (pinfunction "PE4_3") (pintype "passive"))
    )
    (net (code "98") (name "unconnected-(IC2-PE5-Pad4)") (class "Default")
      (node (ref "IC2") (pin "4") (pinfunction "PE5_4") (pintype "passive"))
    )
    (net (code "99") (name "unconnected-(IC2-PE6-Pad5)") (class "Default")
      (node (ref "IC2") (pin "5") (pinfunction "PE6_5") (pintype "passive"))
    )
    (net (code "100") (name "unconnected-(IC2-PE15-Pad45)") (class "Default")
      (node (ref "IC2") (pin "45") (pinfunction "PE15_45") (pintype "passive"))
    )
    (net (code "101") (name "unconnected-(J4-SBU1-Pad10)") (class "Default")
      (node (ref "J4") (pin "10") (pinfunction "SBU1_10") (pintype "passive+no_connect"))
    )
    (net (code "102") (name "unconnected-(J4-SBU2-Pad4)") (class "Default")
      (node (ref "J4") (pin "4") (pinfunction "SBU2_4") (pintype "passive+no_connect"))
    )
  )
)
